# div59_eagle.net
KiCad netlist of a schematic drawn in EAGLE
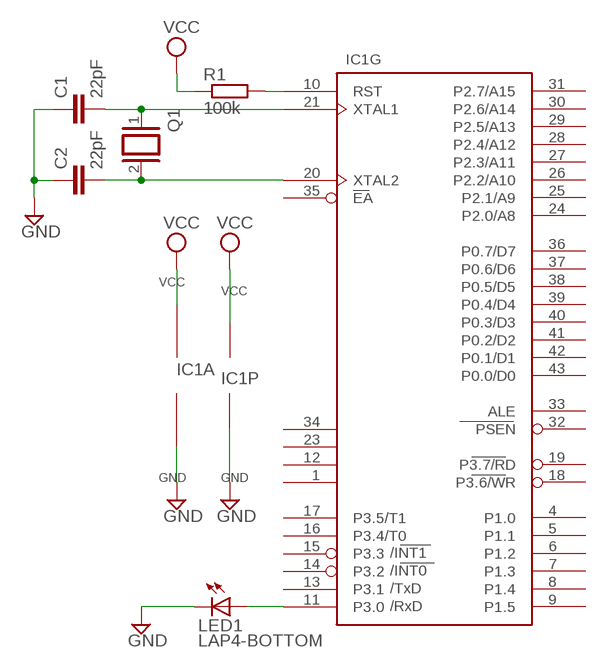
[diagram p0: schematic, sheet 1]

(export (version "E")
  (design (tool "Eeschema 10.0.6"))
  (components
    (comp (ref "C1")
      (value "22pF")
      (footprint "eagle-import:C025-024X044")
      (libsource (lib "eagle-import") (part "C-EU025-024X044"))
    )
    (comp (ref "C2")
      (value "22pF")
      (footprint "eagle-import:C025-024X044")
      (libsource (lib "eagle-import") (part "C-EU025-024X044"))
    )
    (comp (ref "IC1")
      (value "80C576SMD")
      (footprint "eagle-import:PLCC44")
      (libsource (lib "eagle-import") (part "80C576SMD"))
    )
    (comp (ref "LED1")
      (value "LAP4-BOTTOM")
      (footprint "eagle-import:P47F-BOTTOM")
      (libsource (lib "eagle-import") (part "P4-BOTTOMLA"))
    )
    (comp (ref "Q1")
      (value "XTAL/S")
      (footprint "eagle-import:QS")
      (libsource (lib "eagle-import") (part "XTAL/S"))
    )
    (comp (ref "R1")
      (value "100k")
      (footprint "eagle-import:0204V")
      (libsource (lib "eagle-import") (part "R-EU_0204/2V"))
    )
  )
  (nets
    (net (code "1") (name "GND") (class "Default")
      (node (ref "C1") (pin "1") (pinfunction "1_1") (pintype "passive"))
      (node (ref "C2") (pin "1") (pinfunction "1_1") (pintype "passive"))
      (node (ref "IC1") (pin "22") (pinfunction "GND_22") (pintype "power_in"))
      (node (ref "IC1") (pin "3") (pinfunction "AGND_3") (pintype "power_in"))
      (node (ref "LED1") (pin "C") (pinfunction "C_C") (pintype "passive"))
    )
    (net (code "2") (name "Net-(IC1B-P3.0)") (class "Default")
      (node (ref "IC1") (pin "11") (pinfunction "P3.0_11") (pintype "bidirectional"))
      (node (ref "LED1") (pin "A") (pinfunction "A_A") (pintype "passive"))
    )
    (net (code "3") (name "Net-(IC1B-RST)") (class "Default")
      (node (ref "IC1") (pin "10") (pinfunction "RST_10") (pintype "input"))
      (node (ref "R1") (pin "2") (pinfunction "2_2") (pintype "passive"))
    )
    (net (code "4") (name "Net-(IC1B-XTAL1)") (class "Default")
      (node (ref "C1") (pin "2") (pinfunction "2_2") (pintype "passive"))
      (node (ref "IC1") (pin "21") (pinfunction "XTAL1_21") (pintype "input"))
      (node (ref "Q1") (pin "1") (pinfunction "1_1") (pintype "passive"))
    )
    (net (code "5") (name "Net-(IC1B-XTAL2)") (class "Default")
      (node (ref "C2") (pin "2") (pinfunction "2_2") (pintype "passive"))
      (node (ref "IC1") (pin "20") (pinfunction "XTAL2_20") (pintype "input"))
      (node (ref "Q1") (pin "2") (pinfunction "2_2") (pintype "passive"))
    )
    (net (code "6") (name "VCC") (class "Default")
      (node (ref "IC1") (pin "2") (pinfunction "AVCC_2") (pintype "power_in"))
      (node (ref "IC1") (pin "44") (pinfunction "VCC_44") (pintype "power_in"))
      (node (ref "R1") (pin "1") (pinfunction "1_1") (pintype "passive"))
    )
    (net (code "7") (name "unconnected-(IC1B-ALE-Pad33)") (class "Default")
      (node (ref "IC1") (pin "33") (pinfunction "ALE_33") (pintype "output"))
    )
    (net (code "8") (name "unconnected-(IC1B-EA-Pad35)") (class "Default")
      (node (ref "IC1") (pin "35") (pinfunction "EA_35") (pintype "input"))
    )
    (net (code "9") (name "unconnected-(IC1B-NC-Pad1)") (class "Default")
      (node (ref "IC1") (pin "1") (pinfunction "NC_1") (pintype "no_connect"))
    )
    (net (code "10") (name "unconnected-(IC1B-NC-Pad12)") (class "Default")
      (node (ref "IC1") (pin "12") (pinfunction "NC_12") (pintype "no_connect"))
    )
    (net (code "11") (name "unconnected-(IC1B-NC-Pad23)") (class "Default")
      (node (ref "IC1") (pin "23") (pinfunction "NC_23") (pintype "no_connect"))
    )
    (net (code "12") (name "unconnected-(IC1B-NC-Pad34)") (class "Default")
      (node (ref "IC1") (pin "34") (pinfunction "NC_34") (pintype "no_connect"))
    )
    (net (code "13") (name "unconnected-(IC1B-P0.0{slash}D0-Pad43)") (class "Default")
      (node (ref "IC1") (pin "43") (pinfunction "P0.0/D0_43") (pintype "bidirectional"))
    )
    (net (code "14") (name "unconnected-(IC1B-P0.1{slash}D1-Pad42)") (class "Default")
      (node (ref "IC1") (pin "42") (pinfunction "P0.1/D1_42") (pintype "bidirectional"))
    )
    (net (code "15") (name "unconnected-(IC1B-P0.2{slash}D2-Pad41)") (class "Default")
      (node (ref "IC1") (pin "41") (pinfunction "P0.2/D2_41") (pintype "bidirectional"))
    )
    (net (code "16") (name "unconnected-(IC1B-P0.3{slash}D3-Pad40)") (class "Default")
      (node (ref "IC1") (pin "40") (pinfunction "P0.3/D3_40") (pintype "bidirectional"))
    )
    (net (code "17") (name "unconnected-(IC1B-P0.4{slash}D4-Pad39)") (class "Default")
      (node (ref "IC1") (pin "39") (pinfunction "P0.4/D4_39") (pintype "bidirectional"))
    )
    (net (code "18") (name "unconnected-(IC1B-P0.5{slash}D5-Pad38)") (class "Default")
      (node (ref "IC1") (pin "38") (pinfunction "P0.5/D5_38") (pintype "bidirectional"))
    )
    (net (code "19") (name "unconnected-(IC1B-P0.6{slash}D6-Pad37)") (class "Default")
      (node (ref "IC1") (pin "37") (pinfunction "P0.6/D6_37") (pintype "bidirectional"))
    )
    (net (code "20") (name "unconnected-(IC1B-P0.7{slash}D7-Pad36)") (class "Default")
      (node (ref "IC1") (pin "36") (pinfunction "P0.7/D7_36") (pintype "bidirectional"))
    )
    (net (code "21") (name "unconnected-(IC1B-P1.0-Pad4)") (class "Default")
      (node (ref "IC1") (pin "4") (pinfunction "P1.0_4") (pintype "bidirectional"))
    )
    (net (code "22") (name "unconnected-(IC1B-P1.1-Pad5)") (class "Default")
      (node (ref "IC1") (pin "5") (pinfunction "P1.1_5") (pintype "bidirectional"))
    )
    (net (code "23") (name "unconnected-(IC1B-P1.2-Pad6)") (class "Default")
      (node (ref "IC1") (pin "6") (pinfunction "P1.2_6") (pintype "bidirectional"))
    )
    (net (code "24") (name "unconnected-(IC1B-P1.3-Pad7)") (class "Default")
      (node (ref "IC1") (pin "7") (pinfunction "P1.3_7") (pintype "bidirectional"))
    )
    (net (code "25") (name "unconnected-(IC1B-P1.4-Pad8)") (class "Default")
      (node (ref "IC1") (pin "8") (pinfunction "P1.4_8") (pintype "bidirectional"))
    )
    (net (code "26") (name "unconnected-(IC1B-P1.5-Pad9)") (class "Default")
      (node (ref "IC1") (pin "9") (pinfunction "P1.5_9") (pintype "bidirectional"))
    )
    (net (code "27") (name "unconnected-(IC1B-P2.0{slash}A8-Pad24)") (class "Default")
      (node (ref "IC1") (pin "24") (pinfunction "P2.0/A8_24") (pintype "bidirectional"))
    )
    (net (code "28") (name "unconnected-(IC1B-P2.1{slash}A9-Pad25)") (class "Default")
      (node (ref "IC1") (pin "25") (pinfunction "P2.1/A9_25") (pintype "bidirectional"))
    )
    (net (code "29") (name "unconnected-(IC1B-P2.2{slash}A10-Pad26)") (class "Default")
      (node (ref "IC1") (pin "26") (pinfunction "P2.2/A10_26") (pintype "bidirectional"))
    )
    (net (code "30") (name "unconnected-(IC1B-P2.3{slash}A11-Pad27)") (class "Default")
      (node (ref "IC1") (pin "27") (pinfunction "P2.3/A11_27") (pintype "bidirectional"))
    )
    (net (code "31") (name "unconnected-(IC1B-P2.4{slash}A12-Pad28)") (class "Default")
      (node (ref "IC1") (pin "28") (pinfunction "P2.4/A12_28") (pintype "bidirectional"))
    )
    (net (code "32") (name "unconnected-(IC1B-P2.5{slash}A13-Pad29)") (class "Default")
      (node (ref "IC1") (pin "29") (pinfunction "P2.5/A13_29") (pintype "bidirectional"))
    )
    (net (code "33") (name "unconnected-(IC1B-P2.6{slash}A14-Pad30)") (class "Default")
      (node (ref "IC1") (pin "30") (pinfunction "P2.6/A14_30") (pintype "bidirectional"))
    )
    (net (code "34") (name "unconnected-(IC1B-P2.7{slash}A15-Pad31)") (class "Default")
      (node (ref "IC1") (pin "31") (pinfunction "P2.7/A15_31") (pintype "bidirectional"))
    )
    (net (code "35") (name "unconnected-(IC1B-P3.1-Pad13)") (class "Default")
      (node (ref "IC1") (pin "13") (pinfunction "P3.1_13") (pintype "bidirectional"))
    )
    (net (code "36") (name "unconnected-(IC1B-P3.2-Pad14)") (class "Default")
      (node (ref "IC1") (pin "14") (pinfunction "P3.2_14") (pintype "bidirectional"))
    )
    (net (code "37") (name "unconnected-(IC1B-P3.3-Pad15)") (class "Default")
      (node (ref "IC1") (pin "15") (pinfunction "P3.3_15") (pintype "bidirectional"))
    )
    (net (code "38") (name "unconnected-(IC1B-P3.4{slash}T0-Pad16)") (class "Default")
      (node (ref "IC1") (pin "16") (pinfunction "P3.4/T0_16") (pintype "bidirectional"))
    )
    (net (code "39") (name "unconnected-(IC1B-P3.5{slash}T1-Pad17)") (class "Default")
      (node (ref "IC1") (pin "17") (pinfunction "P3.5/T1_17") (pintype "bidirectional"))
    )
    (net (code "40") (name "unconnected-(IC1B-P3.6{slash}WR-Pad18)") (class "Default")
      (node (ref "IC1") (pin "18") (pinfunction "P3.6/WR_18") (pintype "bidirectional"))
    )
    (net (code "41") (name "unconnected-(IC1B-P3.7{slash}RD-Pad19)") (class "Default")
      (node (ref "IC1") (pin "19") (pinfunction "P3.7/RD_19") (pintype "bidirectional"))
    )
    (net (code "42") (name "unconnected-(IC1B-PSEN-Pad32)") (class "Default")
      (node (ref "IC1") (pin "32") (pinfunction "PSEN_32") (pintype "output"))
    )
  )
)
